# OpenWest_2015.net
KiCad netlist of a schematic drawn in EAGLE
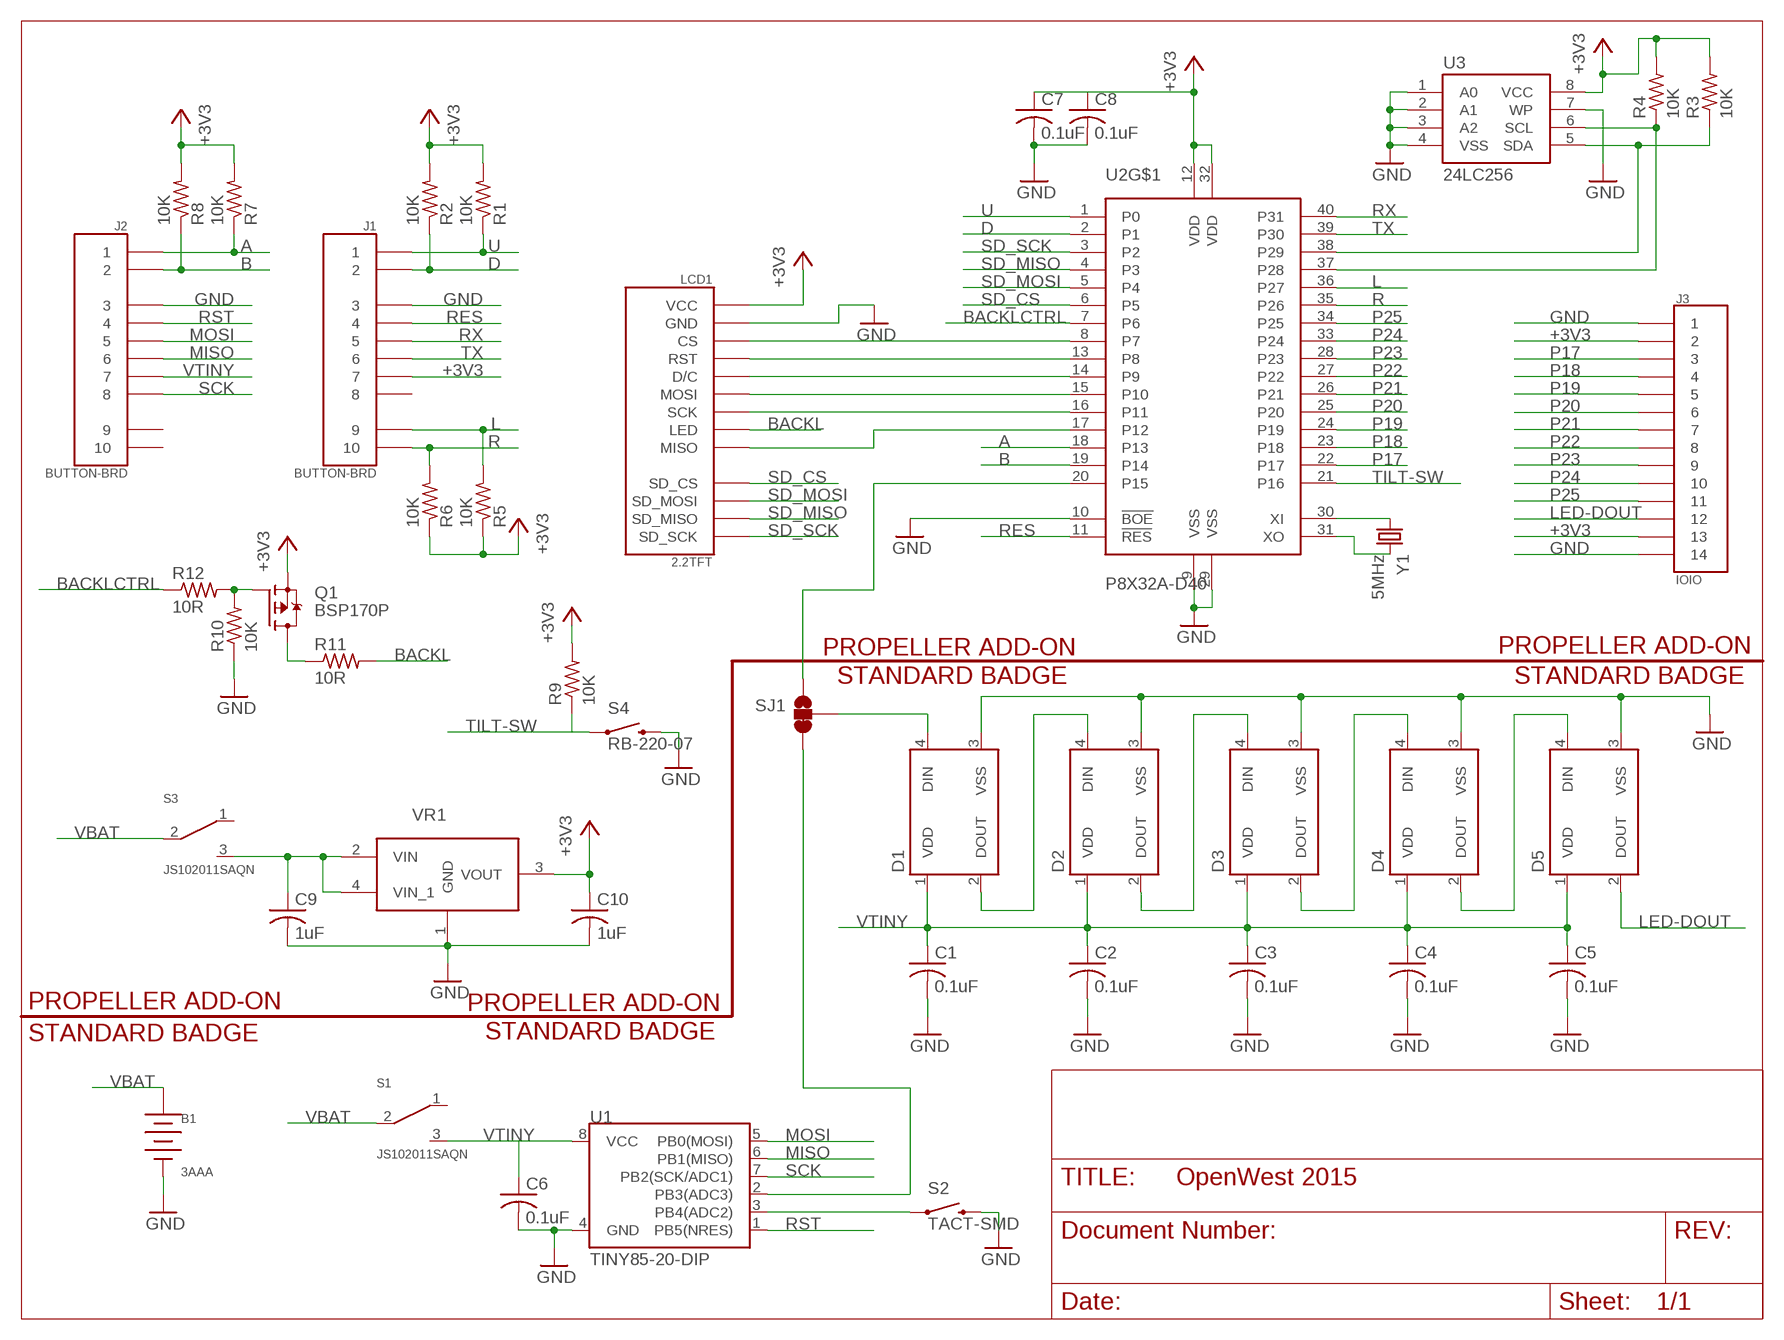
[diagram p0: schematic, sheet 1]

(export (version "E")
  (design (tool "Eeschema 10.0.6"))
  (components
    (comp (ref "B1")
      (value "3AAA")
      (footprint "eagle-import:FLYING-LEADS")
      (libsource (lib "eagle-import") (part "3AAA"))
    )
    (comp (ref "C1")
      (value "0.1uF")
      (footprint "eagle-import:C1206K")
      (libsource (lib "eagle-import") (part "C-USC1206K"))
    )
    (comp (ref "C2")
      (value "0.1uF")
      (footprint "eagle-import:C1206K")
      (libsource (lib "eagle-import") (part "C-USC1206K"))
    )
    (comp (ref "C3")
      (value "0.1uF")
      (footprint "eagle-import:C1206K")
      (libsource (lib "eagle-import") (part "C-USC1206K"))
    )
    (comp (ref "C4")
      (value "0.1uF")
      (footprint "eagle-import:C1206K")
      (libsource (lib "eagle-import") (part "C-USC1206K"))
    )
    (comp (ref "C5")
      (value "0.1uF")
      (footprint "eagle-import:C1206K")
      (libsource (lib "eagle-import") (part "C-USC1206K"))
    )
    (comp (ref "C6")
      (value "0.1uF")
      (footprint "eagle-import:C1206K")
      (libsource (lib "eagle-import") (part "C-USC1206K"))
    )
    (comp (ref "C7")
      (value "0.1uF")
      (footprint "eagle-import:C1206K")
      (libsource (lib "eagle-import") (part "C-USC1206K"))
    )
    (comp (ref "C8")
      (value "0.1uF")
      (footprint "eagle-import:C1206K")
      (libsource (lib "eagle-import") (part "C-USC1206K"))
    )
    (comp (ref "C9")
      (value "1uF")
      (footprint "eagle-import:C1206K")
      (libsource (lib "eagle-import") (part "C-USC1206K"))
    )
    (comp (ref "C10")
      (value "1uF")
      (footprint "eagle-import:C1206K")
      (libsource (lib "eagle-import") (part "C-USC1206K"))
    )
    (comp (ref "D1")
      (value "WS2812B")
      (footprint "eagle-import:WS2812B")
      (libsource (lib "eagle-import") (part "WS2812B"))
    )
    (comp (ref "D2")
      (value "WS2812B")
      (footprint "eagle-import:WS2812B")
      (libsource (lib "eagle-import") (part "WS2812B"))
    )
    (comp (ref "D3")
      (value "WS2812B")
      (footprint "eagle-import:WS2812B")
      (libsource (lib "eagle-import") (part "WS2812B"))
    )
    (comp (ref "D4")
      (value "WS2812B")
      (footprint "eagle-import:WS2812B")
      (libsource (lib "eagle-import") (part "WS2812B"))
    )
    (comp (ref "D5")
      (value "WS2812B")
      (footprint "eagle-import:WS2812B")
      (libsource (lib "eagle-import") (part "WS2812B"))
    )
    (comp (ref "J1")
      (value "BUTTON-BRD")
      (footprint "eagle-import:BUTTON-BRD")
      (libsource (lib "eagle-import") (part "BUTTON-BRD"))
    )
    (comp (ref "J2")
      (value "BUTTON-BRD")
      (footprint "eagle-import:BUTTON-BRD")
      (libsource (lib "eagle-import") (part "BUTTON-BRD"))
    )
    (comp (ref "J3")
      (value "IOIO")
      (footprint "eagle-import:IOIO")
      (libsource (lib "eagle-import") (part "IOIO"))
    )
    (comp (ref "LCD1")
      (value "2.2TFT")
      (footprint "eagle-import:2.2TFT")
      (libsource (lib "eagle-import") (part "2.2TFT"))
    )
    (comp (ref "Q1")
      (value "BSP170P")
      (footprint "eagle-import:SOT223")
      (libsource (lib "eagle-import") (part "BSP170P"))
    )
    (comp (ref "R1")
      (value "10K")
      (footprint "eagle-import:R1206")
      (libsource (lib "eagle-import") (part "R-US_R1206"))
    )
    (comp (ref "R2")
      (value "10K")
      (footprint "eagle-import:R1206")
      (libsource (lib "eagle-import") (part "R-US_R1206"))
    )
    (comp (ref "R3")
      (value "10K")
      (footprint "eagle-import:R1206")
      (libsource (lib "eagle-import") (part "R-US_R1206"))
    )
    (comp (ref "R4")
      (value "10K")
      (footprint "eagle-import:R1206")
      (libsource (lib "eagle-import") (part "R-US_R1206"))
    )
    (comp (ref "R5")
      (value "10K")
      (footprint "eagle-import:R1206")
      (libsource (lib "eagle-import") (part "R-US_R1206"))
    )
    (comp (ref "R6")
      (value "10K")
      (footprint "eagle-import:R1206")
      (libsource (lib "eagle-import") (part "R-US_R1206"))
    )
    (comp (ref "R7")
      (value "10K")
      (footprint "eagle-import:R1206")
      (libsource (lib "eagle-import") (part "R-US_R1206"))
    )
    (comp (ref "R8")
      (value "10K")
      (footprint "eagle-import:R1206")
      (libsource (lib "eagle-import") (part "R-US_R1206"))
    )
    (comp (ref "R9")
      (value "10K")
      (footprint "eagle-import:R1206")
      (libsource (lib "eagle-import") (part "R-US_R1206"))
    )
    (comp (ref "R10")
      (value "10K")
      (footprint "eagle-import:R1206")
      (libsource (lib "eagle-import") (part "R-US_R1206"))
    )
    (comp (ref "R11")
      (value "10R")
      (footprint "eagle-import:R1206")
      (libsource (lib "eagle-import") (part "R-US_R1206"))
    )
    (comp (ref "R12")
      (value "10R")
      (footprint "eagle-import:R1206")
      (libsource (lib "eagle-import") (part "R-US_R1206"))
    )
    (comp (ref "S1")
      (value "JS102011SAQN")
      (footprint "eagle-import:SAQN")
      (libsource (lib "eagle-import") (part "JS102011SAQN"))
    )
    (comp (ref "S2")
      (value "TACT-SMD")
      (footprint "eagle-import:TACT-SMD")
      (libsource (lib "eagle-import") (part "TACT-SMD"))
    )
    (comp (ref "S3")
      (value "JS102011SAQN")
      (footprint "eagle-import:SAQN")
      (libsource (lib "eagle-import") (part "JS102011SAQN"))
    )
    (comp (ref "S4")
      (value "RB-220-07")
      (footprint "eagle-import:SPST")
      (libsource (lib "eagle-import") (part "RB-220-07"))
    )
    (comp (ref "SJ1")
      (value "JUMPER-PAD-3-2OF3_NC_BY_TRACE_LARGE")
      (footprint "eagle-import:PAD-JUMPER-3-2OF3_NC_BY_TRACE_YES_SILK_LARGE")
      (libsource (lib "eagle-import") (part "JUMPER-PAD-3-2OF3_NC_BY_TRACE_LARGE"))
    )
    (comp (ref "U1")
      (value "TINY85-20-DIP")
      (footprint "eagle-import:DIP08")
      (libsource (lib "eagle-import") (part "ATTINY45TINY85-20-DIP"))
    )
    (comp (ref "U2")
      (value "P8X32A-D40")
      (footprint "eagle-import:DIP-40")
      (libsource (lib "eagle-import") (part "P8X32A-D40"))
    )
    (comp (ref "U3")
      (value "24LC256")
      (footprint "eagle-import:DIP08")
      (libsource (lib "eagle-import") (part "24LC64"))
    )
    (comp (ref "VR1")
      (value "MCP17-MCP1700T-3302E/MB")
      (footprint "eagle-import:SOT150P400X160-4N")
      (fields (field (name "MPN") "MCP1700T-3302E/MB"))
      (libsource (lib "eagle-import") (part "MCP17-MCP1700T-3302E/MB"))
    )
    (comp (ref "Y1")
      (value "5MHz")
      (footprint "eagle-import:CRYSTAL-SMD")
      (libsource (lib "eagle-import") (part "CRYSTAL-TH-11.5X5MM"))
    )
  )
  (nets
    (net (code "1") (name "+3V3") (class "Default")
      (node (ref "C10") (pin "1") (pinfunction "1_1") (pintype "passive"))
      (node (ref "C7") (pin "1") (pinfunction "1_1") (pintype "passive"))
      (node (ref "C8") (pin "1") (pinfunction "1_1") (pintype "passive"))
      (node (ref "J1") (pin "7") (pinfunction "7_7") (pintype "bidirectional"))
      (node (ref "J3") (pin "P$13") (pinfunction "13_P$13") (pintype "bidirectional"))
      (node (ref "J3") (pin "P$2") (pinfunction "2_P$2") (pintype "bidirectional"))
      (node (ref "LCD1") (pin "VCC") (pinfunction "VCC_VCC") (pintype "bidirectional"))
      (node (ref "Q1") (pin "3") (pinfunction "S_3") (pintype "passive"))
      (node (ref "R1") (pin "2") (pinfunction "2_2") (pintype "passive"))
      (node (ref "R2") (pin "2") (pinfunction "2_2") (pintype "passive"))
      (node (ref "R3") (pin "2") (pinfunction "2_2") (pintype "passive"))
      (node (ref "R4") (pin "2") (pinfunction "2_2") (pintype "passive"))
      (node (ref "R5") (pin "1") (pinfunction "1_1") (pintype "passive"))
      (node (ref "R6") (pin "1") (pinfunction "1_1") (pintype "passive"))
      (node (ref "R7") (pin "2") (pinfunction "2_2") (pintype "passive"))
      (node (ref "R8") (pin "2") (pinfunction "2_2") (pintype "passive"))
      (node (ref "R9") (pin "2") (pinfunction "2_2") (pintype "passive"))
      (node (ref "U2") (pin "12") (pinfunction "VDD_12") (pintype "input"))
      (node (ref "U2") (pin "32") (pinfunction "VDD_32") (pintype "input"))
      (node (ref "U3") (pin "8") (pinfunction "VCC_8") (pintype "power_in"))
      (node (ref "VR1") (pin "3") (pinfunction "VOUT_3") (pintype "output"))
    )
    (net (code "2") (name "/A") (class "Default")
      (node (ref "J2") (pin "1") (pinfunction "1_1") (pintype "bidirectional"))
      (node (ref "R7") (pin "1") (pinfunction "1_1") (pintype "passive"))
      (node (ref "U2") (pin "18") (pinfunction "P13_18") (pintype "bidirectional"))
    )
    (net (code "3") (name "/B") (class "Default")
      (node (ref "J2") (pin "2") (pinfunction "2_2") (pintype "bidirectional"))
      (node (ref "R8") (pin "1") (pinfunction "1_1") (pintype "passive"))
      (node (ref "U2") (pin "19") (pinfunction "P14_19") (pintype "bidirectional"))
    )
    (net (code "4") (name "/BACKL") (class "Default")
      (node (ref "LCD1") (pin "LED") (pinfunction "LED_LED") (pintype "bidirectional"))
      (node (ref "R11") (pin "2") (pinfunction "2_2") (pintype "passive"))
    )
    (net (code "5") (name "/BACKLCTRL") (class "Default")
      (node (ref "R12") (pin "1") (pinfunction "1_1") (pintype "passive"))
      (node (ref "U2") (pin "7") (pinfunction "P6_7") (pintype "bidirectional"))
    )
    (net (code "6") (name "/D") (class "Default")
      (node (ref "J1") (pin "2") (pinfunction "2_2") (pintype "bidirectional"))
      (node (ref "R2") (pin "1") (pinfunction "1_1") (pintype "passive"))
      (node (ref "U2") (pin "2") (pinfunction "P1_2") (pintype "bidirectional"))
    )
    (net (code "7") (name "/L") (class "Default")
      (node (ref "J1") (pin "9") (pinfunction "9_9") (pintype "bidirectional"))
      (node (ref "R5") (pin "2") (pinfunction "2_2") (pintype "passive"))
      (node (ref "U2") (pin "36") (pinfunction "P27_36") (pintype "bidirectional"))
    )
    (net (code "8") (name "/LED-DOUT") (class "Default")
      (node (ref "D5") (pin "2") (pinfunction "DOUT_2") (pintype "output"))
      (node (ref "J3") (pin "P$12") (pinfunction "12_P$12") (pintype "bidirectional"))
    )
    (net (code "9") (name "/MISO") (class "Default")
      (node (ref "J2") (pin "6") (pinfunction "6_6") (pintype "bidirectional"))
      (node (ref "U1") (pin "6") (pinfunction "PB1(MISO)_6") (pintype "bidirectional"))
    )
    (net (code "10") (name "/MOSI") (class "Default")
      (node (ref "J2") (pin "5") (pinfunction "5_5") (pintype "bidirectional"))
      (node (ref "U1") (pin "5") (pinfunction "PB0(MOSI)_5") (pintype "bidirectional"))
    )
    (net (code "11") (name "/P17") (class "Default")
      (node (ref "J3") (pin "P$3") (pinfunction "3_P$3") (pintype "bidirectional"))
      (node (ref "U2") (pin "22") (pinfunction "P17_22") (pintype "bidirectional"))
    )
    (net (code "12") (name "/P18") (class "Default")
      (node (ref "J3") (pin "P$4") (pinfunction "4_P$4") (pintype "bidirectional"))
      (node (ref "U2") (pin "23") (pinfunction "P18_23") (pintype "bidirectional"))
    )
    (net (code "13") (name "/P19") (class "Default")
      (node (ref "J3") (pin "P$5") (pinfunction "5_P$5") (pintype "bidirectional"))
      (node (ref "U2") (pin "24") (pinfunction "P19_24") (pintype "bidirectional"))
    )
    (net (code "14") (name "/P20") (class "Default")
      (node (ref "J3") (pin "P$6") (pinfunction "6_P$6") (pintype "bidirectional"))
      (node (ref "U2") (pin "25") (pinfunction "P20_25") (pintype "bidirectional"))
    )
    (net (code "15") (name "/P21") (class "Default")
      (node (ref "J3") (pin "P$7") (pinfunction "7_P$7") (pintype "bidirectional"))
      (node (ref "U2") (pin "26") (pinfunction "P21_26") (pintype "bidirectional"))
    )
    (net (code "16") (name "/P22") (class "Default")
      (node (ref "J3") (pin "P$8") (pinfunction "8_P$8") (pintype "bidirectional"))
      (node (ref "U2") (pin "27") (pinfunction "P22_27") (pintype "bidirectional"))
    )
    (net (code "17") (name "/P23") (class "Default")
      (node (ref "J3") (pin "P$9") (pinfunction "9_P$9") (pintype "bidirectional"))
      (node (ref "U2") (pin "28") (pinfunction "P23_28") (pintype "bidirectional"))
    )
    (net (code "18") (name "/P24") (class "Default")
      (node (ref "J3") (pin "P$10") (pinfunction "10_P$10") (pintype "bidirectional"))
      (node (ref "U2") (pin "33") (pinfunction "P24_33") (pintype "bidirectional"))
    )
    (net (code "19") (name "/P25") (class "Default")
      (node (ref "J3") (pin "P$11") (pinfunction "11_P$11") (pintype "bidirectional"))
      (node (ref "U2") (pin "34") (pinfunction "P25_34") (pintype "bidirectional"))
    )
    (net (code "20") (name "/R") (class "Default")
      (node (ref "J1") (pin "10") (pinfunction "10_10") (pintype "bidirectional"))
      (node (ref "R6") (pin "2") (pinfunction "2_2") (pintype "passive"))
      (node (ref "U2") (pin "35") (pinfunction "P26_35") (pintype "bidirectional"))
    )
    (net (code "21") (name "/RES") (class "Default")
      (node (ref "J1") (pin "4") (pinfunction "4_4") (pintype "bidirectional"))
      (node (ref "U2") (pin "11") (pinfunction "~{RES}_11") (pintype "bidirectional"))
    )
    (net (code "22") (name "/RST") (class "Default")
      (node (ref "J2") (pin "4") (pinfunction "4_4") (pintype "bidirectional"))
      (node (ref "U1") (pin "1") (pinfunction "PB5(NRES)_1") (pintype "bidirectional"))
    )
    (net (code "23") (name "/RX") (class "Default")
      (node (ref "J1") (pin "5") (pinfunction "5_5") (pintype "bidirectional"))
      (node (ref "U2") (pin "40") (pinfunction "P31_40") (pintype "bidirectional"))
    )
    (net (code "24") (name "/SCK") (class "Default")
      (node (ref "J2") (pin "8") (pinfunction "8_8") (pintype "bidirectional"))
      (node (ref "U1") (pin "7") (pinfunction "PB2(SCK/ADC1)_7") (pintype "bidirectional"))
    )
    (net (code "25") (name "/SD_CS") (class "Default")
      (node (ref "LCD1") (pin "SD_CS") (pinfunction "SD_CS_SD_CS") (pintype "bidirectional"))
      (node (ref "U2") (pin "6") (pinfunction "P5_6") (pintype "bidirectional"))
    )
    (net (code "26") (name "/SD_MISO") (class "Default")
      (node (ref "LCD1") (pin "SD_MISO") (pinfunction "SD_MISO_SD_MISO") (pintype "bidirectional"))
      (node (ref "U2") (pin "4") (pinfunction "P3_4") (pintype "bidirectional"))
    )
    (net (code "27") (name "/SD_MOSI") (class "Default")
      (node (ref "LCD1") (pin "SD_MOSI") (pinfunction "SD_MOSI_SD_MOSI") (pintype "bidirectional"))
      (node (ref "U2") (pin "5") (pinfunction "P4_5") (pintype "bidirectional"))
    )
    (net (code "28") (name "/SD_SCK") (class "Default")
      (node (ref "LCD1") (pin "SD_SCK") (pinfunction "SD_SCK_SD_SCK") (pintype "bidirectional"))
      (node (ref "U2") (pin "3") (pinfunction "P2_3") (pintype "bidirectional"))
    )
    (net (code "29") (name "/TILT-SW") (class "Default")
      (node (ref "R9") (pin "1") (pinfunction "1_1") (pintype "passive"))
      (node (ref "S4") (pin "1") (pinfunction "1_1") (pintype "passive"))
      (node (ref "U2") (pin "21") (pinfunction "P16_21") (pintype "bidirectional"))
    )
    (net (code "30") (name "/TX") (class "Default")
      (node (ref "J1") (pin "6") (pinfunction "6_6") (pintype "bidirectional"))
      (node (ref "U2") (pin "39") (pinfunction "P30_39") (pintype "bidirectional"))
    )
    (net (code "31") (name "/U") (class "Default")
      (node (ref "J1") (pin "1") (pinfunction "1_1") (pintype "bidirectional"))
      (node (ref "R1") (pin "1") (pinfunction "1_1") (pintype "passive"))
      (node (ref "U2") (pin "1") (pinfunction "P0_1") (pintype "bidirectional"))
    )
    (net (code "32") (name "/VBAT") (class "Default")
      (node (ref "B1") (pin "+") (pinfunction "+_+") (pintype "bidirectional"))
      (node (ref "S1") (pin "2") (pinfunction "P2_2") (pintype "bidirectional"))
      (node (ref "S3") (pin "2") (pinfunction "P2_2") (pintype "bidirectional"))
    )
    (net (code "33") (name "/VTINY") (class "Default")
      (node (ref "C1") (pin "1") (pinfunction "1_1") (pintype "passive"))
      (node (ref "C2") (pin "1") (pinfunction "1_1") (pintype "passive"))
      (node (ref "C3") (pin "1") (pinfunction "1_1") (pintype "passive"))
      (node (ref "C4") (pin "1") (pinfunction "1_1") (pintype "passive"))
      (node (ref "C5") (pin "1") (pinfunction "1_1") (pintype "passive"))
      (node (ref "C6") (pin "1") (pinfunction "1_1") (pintype "passive"))
      (node (ref "D1") (pin "1") (pinfunction "VDD_1") (pintype "power_in"))
      (node (ref "D2") (pin "1") (pinfunction "VDD_1") (pintype "power_in"))
      (node (ref "D3") (pin "1") (pinfunction "VDD_1") (pintype "power_in"))
      (node (ref "D4") (pin "1") (pinfunction "VDD_1") (pintype "power_in"))
      (node (ref "D5") (pin "1") (pinfunction "VDD_1") (pintype "power_in"))
      (node (ref "J2") (pin "7") (pinfunction "7_7") (pintype "bidirectional"))
      (node (ref "S1") (pin "3") (pinfunction "P3_3") (pintype "bidirectional"))
      (node (ref "U1") (pin "8") (pinfunction "VCC_8") (pintype "bidirectional"))
    )
    (net (code "34") (name "GND") (class "Default")
      (node (ref "B1") (pin "-") (pinfunction "-_-") (pintype "bidirectional"))
      (node (ref "C1") (pin "2") (pinfunction "2_2") (pintype "passive"))
      (node (ref "C10") (pin "2") (pinfunction "2_2") (pintype "passive"))
      (node (ref "C2") (pin "2") (pinfunction "2_2") (pintype "passive"))
      (node (ref "C3") (pin "2") (pinfunction "2_2") (pintype "passive"))
      (node (ref "C4") (pin "2") (pinfunction "2_2") (pintype "passive"))
      (node (ref "C5") (pin "2") (pinfunction "2_2") (pintype "passive"))
      (node (ref "C6") (pin "2") (pinfunction "2_2") (pintype "passive"))
      (node (ref "C7") (pin "2") (pinfunction "2_2") (pintype "passive"))
      (node (ref "C8") (pin "2") (pinfunction "2_2") (pintype "passive"))
      (node (ref "C9") (pin "2") (pinfunction "2_2") (pintype "passive"))
      (node (ref "D1") (pin "3") (pinfunction "VSS_3") (pintype "power_in"))
      (node (ref "D2") (pin "3") (pinfunction "VSS_3") (pintype "power_in"))
      (node (ref "D3") (pin "3") (pinfunction "VSS_3") (pintype "power_in"))
      (node (ref "D4") (pin "3") (pinfunction "VSS_3") (pintype "power_in"))
      (node (ref "D5") (pin "3") (pinfunction "VSS_3") (pintype "power_in"))
      (node (ref "J1") (pin "3") (pinfunction "3_3") (pintype "bidirectional"))
      (node (ref "J2") (pin "3") (pinfunction "3_3") (pintype "bidirectional"))
      (node (ref "J3") (pin "P$1") (pinfunction "1_P$1") (pintype "bidirectional"))
      (node (ref "J3") (pin "P$14") (pinfunction "14_P$14") (pintype "bidirectional"))
      (node (ref "LCD1") (pin "GND") (pinfunction "GND_GND") (pintype "bidirectional"))
      (node (ref "R10") (pin "1") (pinfunction "1_1") (pintype "passive"))
      (node (ref "S2") (pin "P$3") (pinfunction "2_P$3") (pintype "passive"))
      (node (ref "S4") (pin "2") (pinfunction "2_2") (pintype "passive"))
      (node (ref "U1") (pin "4") (pinfunction "GND_4") (pintype "bidirectional"))
      (node (ref "U2") (pin "10") (pinfunction "~{BOE}_10") (pintype "input"))
      (node (ref "U2") (pin "29") (pinfunction "VSS_29") (pintype "input"))
      (node (ref "U2") (pin "9") (pinfunction "VSS_9") (pintype "input"))
      (node (ref "U3") (pin "1") (pinfunction "A0_1") (pintype "bidirectional"))
      (node (ref "U3") (pin "2") (pinfunction "A1_2") (pintype "bidirectional"))
      (node (ref "U3") (pin "3") (pinfunction "A2_3") (pintype "bidirectional"))
      (node (ref "U3") (pin "4") (pinfunction "VSS_4") (pintype "power_in"))
      (node (ref "U3") (pin "7") (pinfunction "WP_7") (pintype "bidirectional"))
      (node (ref "VR1") (pin "1") (pinfunction "GND_1") (pintype "power_in"))
    )
    (net (code "35") (name "Net-(D1-DIN)") (class "Default")
      (node (ref "D1") (pin "4") (pinfunction "DIN_4") (pintype "input"))
      (node (ref "SJ1") (pin "2") (pinfunction "2_2") (pintype "passive"))
    )
    (net (code "36") (name "Net-(D1-DOUT)") (class "Default")
      (node (ref "D1") (pin "2") (pinfunction "DOUT_2") (pintype "output"))
      (node (ref "D2") (pin "4") (pinfunction "DIN_4") (pintype "input"))
    )
    (net (code "37") (name "Net-(D2-DOUT)") (class "Default")
      (node (ref "D2") (pin "2") (pinfunction "DOUT_2") (pintype "output"))
      (node (ref "D3") (pin "4") (pinfunction "DIN_4") (pintype "input"))
    )
    (net (code "38") (name "Net-(D3-DOUT)") (class "Default")
      (node (ref "D3") (pin "2") (pinfunction "DOUT_2") (pintype "output"))
      (node (ref "D4") (pin "4") (pinfunction "DIN_4") (pintype "input"))
    )
    (net (code "39") (name "Net-(D4-DOUT)") (class "Default")
      (node (ref "D4") (pin "2") (pinfunction "DOUT_2") (pintype "output"))
      (node (ref "D5") (pin "4") (pinfunction "DIN_4") (pintype "input"))
    )
    (net (code "40") (name "Net-(Q1-D-Pad2)") (class "Default")
      (node (ref "Q1") (pin "2") (pinfunction "D_2") (pintype "passive"))
      (node (ref "Q1") (pin "4") (pinfunction "D_4") (pintype "passive"))
      (node (ref "R11") (pin "1") (pinfunction "1_1") (pintype "passive"))
    )
    (net (code "41") (name "Net-(Q1-G)") (class "Default")
      (node (ref "Q1") (pin "1") (pinfunction "G_1") (pintype "passive"))
      (node (ref "R10") (pin "2") (pinfunction "2_2") (pintype "passive"))
      (node (ref "R12") (pin "2") (pinfunction "2_2") (pintype "passive"))
    )
    (net (code "42") (name "Net-(S2-1)") (class "Default")
      (node (ref "S2") (pin "P$1") (pinfunction "1_P$1") (pintype "passive"))
      (node (ref "U1") (pin "3") (pinfunction "PB4(ADC2)_3") (pintype "bidirectional"))
    )
    (net (code "43") (name "Net-(S3-P3)") (class "Default")
      (node (ref "C9") (pin "1") (pinfunction "1_1") (pintype "passive"))
      (node (ref "S3") (pin "3") (pinfunction "P3_3") (pintype "bidirectional"))
      (node (ref "VR1") (pin "2") (pinfunction "VIN_2") (pintype "input"))
      (node (ref "VR1") (pin "4") (pinfunction "VIN_1_4") (pintype "input"))
    )
    (net (code "44") (name "Net-(U1-PB3(ADC3))") (class "Default")
      (node (ref "SJ1") (pin "3") (pinfunction "3_3") (pintype "passive"))
      (node (ref "U1") (pin "2") (pinfunction "PB3(ADC3)_2") (pintype "bidirectional"))
    )
    (net (code "45") (name "Net-(U2A-P7)") (class "Default")
      (node (ref "LCD1") (pin "CS") (pinfunction "CS_CS") (pintype "bidirectional"))
      (node (ref "U2") (pin "8") (pinfunction "P7_8") (pintype "bidirectional"))
    )
    (net (code "46") (name "Net-(U2A-P8)") (class "Default")
      (node (ref "LCD1") (pin "RST") (pinfunction "RST_RST") (pintype "bidirectional"))
      (node (ref "U2") (pin "13") (pinfunction "P8_13") (pintype "bidirectional"))
    )
    (net (code "47") (name "Net-(U2A-P9)") (class "Default")
      (node (ref "LCD1") (pin "D/C") (pinfunction "D/C_D/C") (pintype "bidirectional"))
      (node (ref "U2") (pin "14") (pinfunction "P9_14") (pintype "bidirectional"))
    )
    (net (code "48") (name "Net-(U2A-P10)") (class "Default")
      (node (ref "LCD1") (pin "MOSI") (pinfunction "MOSI_MOSI") (pintype "bidirectional"))
      (node (ref "U2") (pin "15") (pinfunction "P10_15") (pintype "bidirectional"))
    )
    (net (code "49") (name "Net-(U2A-P11)") (class "Default")
      (node (ref "LCD1") (pin "SCK") (pinfunction "SCK_SCK") (pintype "bidirectional"))
      (node (ref "U2") (pin "16") (pinfunction "P11_16") (pintype "bidirectional"))
    )
    (net (code "50") (name "Net-(U2A-P12)") (class "Default")
      (node (ref "LCD1") (pin "MISO") (pinfunction "MISO_MISO") (pintype "bidirectional"))
      (node (ref "U2") (pin "17") (pinfunction "P12_17") (pintype "bidirectional"))
    )
    (net (code "51") (name "Net-(U2A-P15)") (class "Default")
      (node (ref "SJ1") (pin "1") (pinfunction "1_1") (pintype "passive"))
      (node (ref "U2") (pin "20") (pinfunction "P15_20") (pintype "bidirectional"))
    )
    (net (code "52") (name "Net-(U2A-P28)") (class "Default")
      (node (ref "R4") (pin "1") (pinfunction "1_1") (pintype "passive"))
      (node (ref "U2") (pin "37") (pinfunction "P28_37") (pintype "bidirectional"))
      (node (ref "U3") (pin "6") (pinfunction "SCL_6") (pintype "bidirectional"))
    )
    (net (code "53") (name "Net-(U2A-P29)") (class "Default")
      (node (ref "R3") (pin "1") (pinfunction "1_1") (pintype "passive"))
      (node (ref "U2") (pin "38") (pinfunction "P29_38") (pintype "bidirectional"))
      (node (ref "U3") (pin "5") (pinfunction "SDA_5") (pintype "bidirectional"))
    )
    (net (code "54") (name "Net-(U2A-XI)") (class "Default")
      (node (ref "U2") (pin "30") (pinfunction "XI_30") (pintype "input"))
      (node (ref "Y1") (pin "P$1") (pinfunction "1_P$1") (pintype "passive"))
    )
    (net (code "55") (name "Net-(U2A-XO)") (class "Default")
      (node (ref "U2") (pin "31") (pinfunction "XO_31") (pintype "output"))
      (node (ref "Y1") (pin "P$2") (pinfunction "2_P$2") (pintype "passive"))
    )
    (net (code "56") (name "unconnected-(J1-Pad8)") (class "Default")
      (node (ref "J1") (pin "8") (pinfunction "8_8") (pintype "bidirectional"))
    )
    (net (code "57") (name "unconnected-(J2-Pad9)") (class "Default")
      (node (ref "J2") (pin "9") (pinfunction "9_9") (pintype "bidirectional"))
    )
    (net (code "58") (name "unconnected-(J2-Pad10)") (class "Default")
      (node (ref "J2") (pin "10") (pinfunction "10_10") (pintype "bidirectional"))
    )
    (net (code "59") (name "unconnected-(S1-P1-Pad1)") (class "Default")
      (node (ref "S1") (pin "1") (pinfunction "P1_1") (pintype "bidirectional"))
    )
    (net (code "60") (name "unconnected-(S3-P1-Pad1)") (class "Default")
      (node (ref "S3") (pin "1") (pinfunction "P1_1") (pintype "bidirectional"))
    )
  )
)
